# Control_de_Juez_V1_0_0.net
KiCad netlist of a schematic drawn in EAGLE
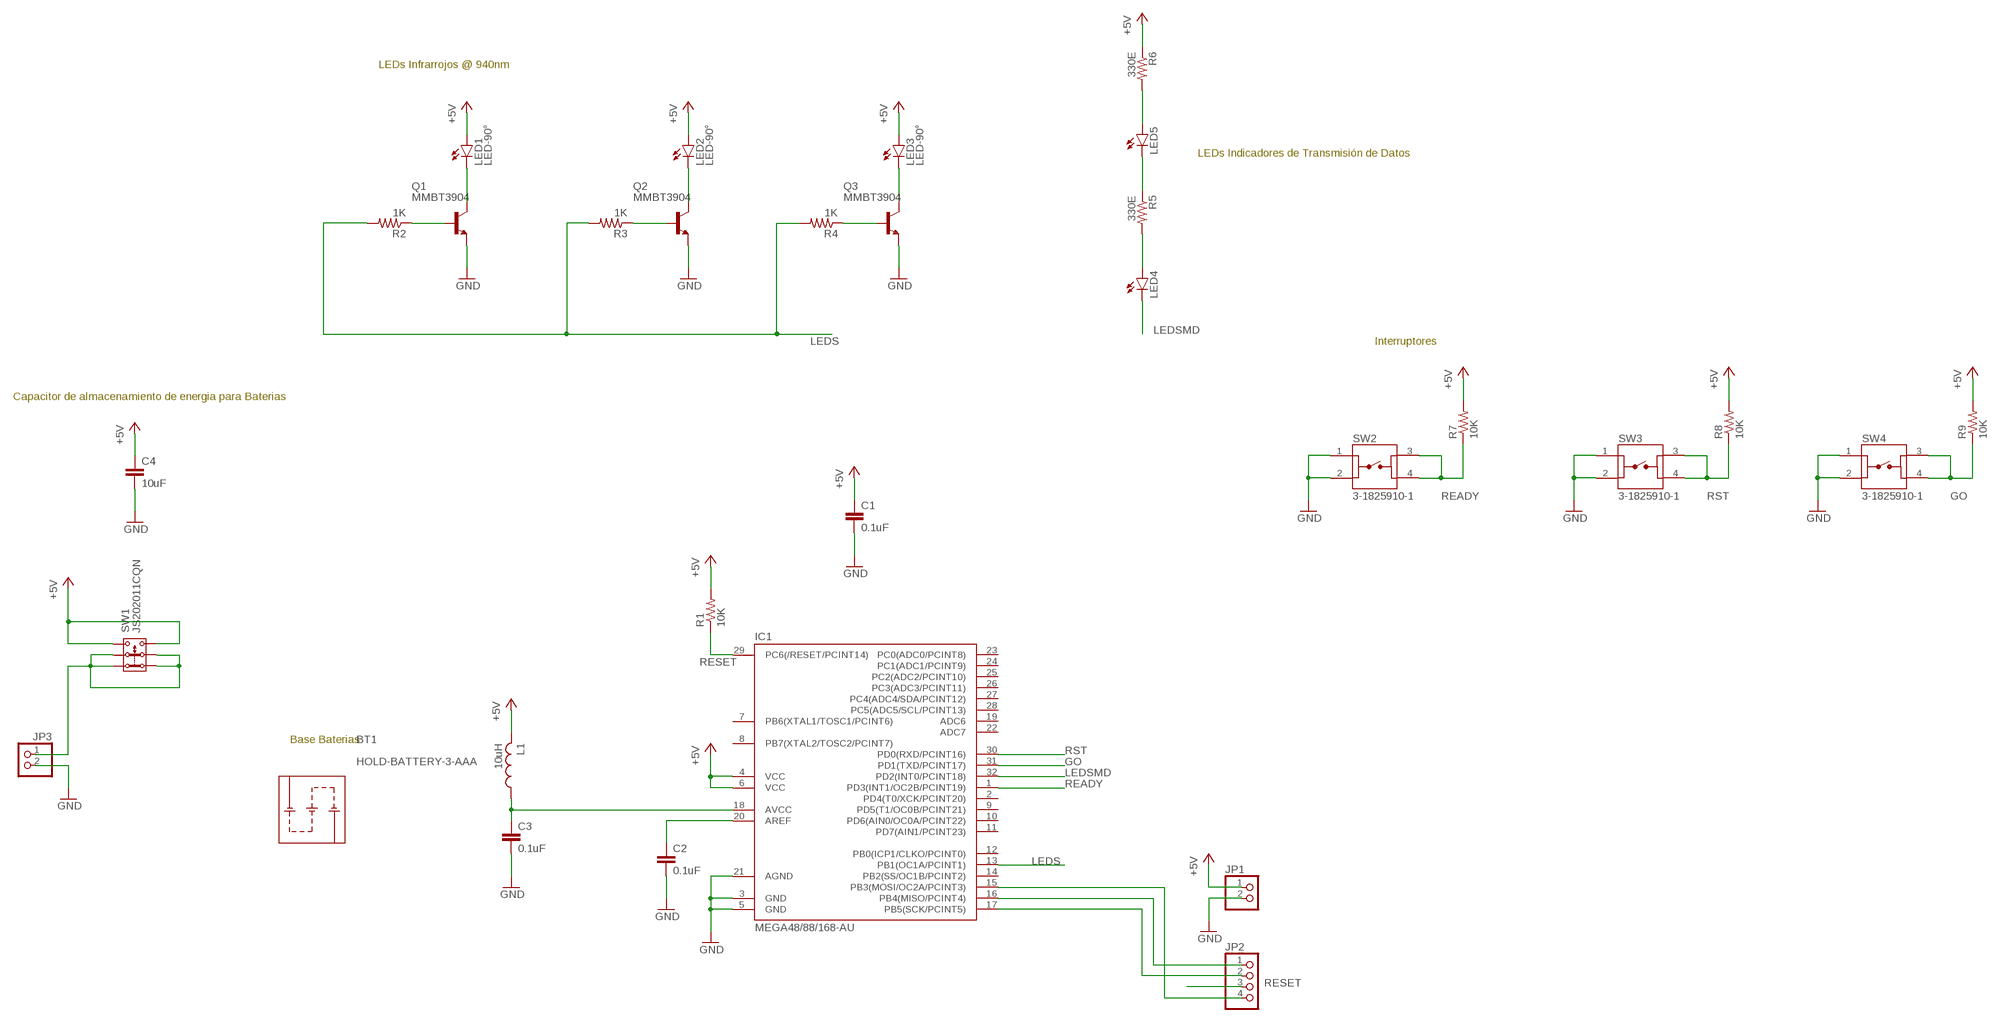
[diagram p0: schematic, sheet 1]

(export (version "E")
  (design (tool "Eeschema 10.0.6"))
  (components
    (comp (ref "BT1")
      (value "HOLD-BATTERY-3-AAA")
      (footprint "eagle-import:HOLDER-3-AAA")
      (libsource (lib "eagle-import") (part "HOLD-BATTERY-3-AAA"))
    )
    (comp (ref "C1")
      (value "0.1uF")
      (footprint "eagle-import:C0603")
      (libsource (lib "eagle-import") (part "C-EUC0603"))
    )
    (comp (ref "C2")
      (value "0.1uF")
      (footprint "eagle-import:C0603")
      (libsource (lib "eagle-import") (part "C-EUC0603"))
    )
    (comp (ref "C3")
      (value "0.1uF")
      (footprint "eagle-import:C0603")
      (libsource (lib "eagle-import") (part "C-EUC0603"))
    )
    (comp (ref "C4")
      (value "10uF")
      (footprint "eagle-import:C0603")
      (libsource (lib "eagle-import") (part "C-EUC0603"))
    )
    (comp (ref "IC1")
      (value "MEGA48/88/168-AU")
      (footprint "eagle-import:TQFP32-08")
      (libsource (lib "eagle-import") (part "MEGA48/88/168-AU"))
    )
    (comp (ref "JP1")
      (value "PINHD-1X02_2.54-S")
      (footprint "eagle-import:1X02-S")
      (libsource (lib "eagle-import") (part "PINHD-1X02_2.54-S"))
    )
    (comp (ref "JP2")
      (value "PINHD-1X04_2.54-S")
      (footprint "eagle-import:1X04-S")
      (libsource (lib "eagle-import") (part "PINHD-1X04_2.54-S"))
    )
    (comp (ref "JP3")
      (value "PINHD-1X02_2.54-S")
      (footprint "eagle-import:1X02-S")
      (libsource (lib "eagle-import") (part "PINHD-1X02_2.54-S"))
    )
    (comp (ref "L1")
      (value "10uH")
      (footprint "eagle-import:L1812")
      (libsource (lib "eagle-import") (part "L-USL1812"))
    )
    (comp (ref "LED1")
      (value "LED-90°")
      (footprint "eagle-import:LED-90°")
      (libsource (lib "eagle-import") (part "LED-90°"))
    )
    (comp (ref "LED2")
      (value "LED-90°")
      (footprint "eagle-import:LED-90°")
      (libsource (lib "eagle-import") (part "LED-90°"))
    )
    (comp (ref "LED3")
      (value "LED-90°")
      (footprint "eagle-import:LED-90°")
      (libsource (lib "eagle-import") (part "LED-90°"))
    )
    (comp (ref "LED4")
      (value "LEDCHIP-LED0603")
      (footprint "eagle-import:CHIP-LED0603")
      (libsource (lib "eagle-import") (part "LEDCHIP-LED0603"))
    )
    (comp (ref "LED5")
      (value "LEDCHIP-LED0603")
      (footprint "eagle-import:CHIP-LED0603")
      (libsource (lib "eagle-import") (part "LEDCHIP-LED0603"))
    )
    (comp (ref "Q1")
      (value "MMBT3904")
      (footprint "eagle-import:SOT23")
      (libsource (lib "eagle-import") (part "MMBT3904"))
    )
    (comp (ref "Q2")
      (value "MMBT3904")
      (footprint "eagle-import:SOT23")
      (libsource (lib "eagle-import") (part "MMBT3904"))
    )
    (comp (ref "Q3")
      (value "MMBT3904")
      (footprint "eagle-import:SOT23")
      (libsource (lib "eagle-import") (part "MMBT3904"))
    )
    (comp (ref "R1")
      (value "10K")
      (footprint "eagle-import:R0603")
      (libsource (lib "eagle-import") (part "R-US_R0603"))
    )
    (comp (ref "R2")
      (value "1K")
      (footprint "eagle-import:R0603")
      (libsource (lib "eagle-import") (part "R-US_R0603"))
    )
    (comp (ref "R3")
      (value "1K")
      (footprint "eagle-import:R0603")
      (libsource (lib "eagle-import") (part "R-US_R0603"))
    )
    (comp (ref "R4")
      (value "1K")
      (footprint "eagle-import:R0603")
      (libsource (lib "eagle-import") (part "R-US_R0603"))
    )
    (comp (ref "R5")
      (value "330E")
      (footprint "eagle-import:R0603")
      (libsource (lib "eagle-import") (part "R-US_R0603"))
    )
    (comp (ref "R6")
      (value "330E")
      (footprint "eagle-import:R0603")
      (libsource (lib "eagle-import") (part "R-US_R0603"))
    )
    (comp (ref "R7")
      (value "10K")
      (footprint "eagle-import:R0603")
      (libsource (lib "eagle-import") (part "R-US_R0603"))
    )
    (comp (ref "R8")
      (value "10K")
      (footprint "eagle-import:R0603")
      (libsource (lib "eagle-import") (part "R-US_R0603"))
    )
    (comp (ref "R9")
      (value "10K")
      (footprint "eagle-import:R0603")
      (libsource (lib "eagle-import") (part "R-US_R0603"))
    )
    (comp (ref "SW1")
      (value "JS202011CQN")
      (footprint "eagle-import:PTH")
      (libsource (lib "eagle-import") (part "JS202011CQN"))
    )
    (comp (ref "SW2")
      (value "3-1825910-1")
      (footprint "eagle-import:TE_3-1825910-1")
      (fields (field (name "MF") "TE Connectivity"))
      (libsource (lib "eagle-import") (part "3-1825910-1"))
    )
    (comp (ref "SW3")
      (value "3-1825910-1")
      (footprint "eagle-import:TE_3-1825910-1")
      (fields (field (name "MF") "TE Connectivity"))
      (libsource (lib "eagle-import") (part "3-1825910-1"))
    )
    (comp (ref "SW4")
      (value "3-1825910-1")
      (footprint "eagle-import:TE_3-1825910-1")
      (fields (field (name "MF") "TE Connectivity"))
      (libsource (lib "eagle-import") (part "3-1825910-1"))
    )
  )
  (nets
    (net (code "1") (name "+5V") (class "Default")
      (node (ref "C1") (pin "1") (pinfunction "1_1") (pintype "passive"))
      (node (ref "C4") (pin "1") (pinfunction "1_1") (pintype "passive"))
      (node (ref "IC1") (pin "4") (pinfunction "VCC_4") (pintype "power_in"))
      (node (ref "IC1") (pin "6") (pinfunction "VCC_6") (pintype "power_in"))
      (node (ref "JP1") (pin "1") (pinfunction "1_1") (pintype "passive"))
      (node (ref "L1") (pin "2") (pinfunction "2_2") (pintype "passive"))
      (node (ref "LED1") (pin "1") (pinfunction "A_1") (pintype "passive"))
      (node (ref "LED2") (pin "1") (pinfunction "A_1") (pintype "passive"))
      (node (ref "LED3") (pin "1") (pinfunction "A_1") (pintype "passive"))
      (node (ref "R1") (pin "2") (pinfunction "2_2") (pintype "passive"))
      (node (ref "R6") (pin "1") (pinfunction "1_1") (pintype "passive"))
      (node (ref "R7") (pin "2") (pinfunction "2_2") (pintype "passive"))
      (node (ref "R8") (pin "2") (pinfunction "2_2") (pintype "passive"))
      (node (ref "R9") (pin "2") (pinfunction "2_2") (pintype "passive"))
      (node (ref "SW1") (pin "3.1") (pinfunction "3.1_3.1") (pintype "passive"))
      (node (ref "SW1") (pin "3.2") (pinfunction "3.2_3.2") (pintype "passive"))
    )
    (net (code "2") (name "/GO") (class "Default")
      (node (ref "IC1") (pin "31") (pinfunction "PD1(TXD/PCINT17)_31") (pintype "bidirectional"))
      (node (ref "R9") (pin "1") (pinfunction "1_1") (pintype "passive"))
      (node (ref "SW4") (pin "3") (pinfunction "3_3") (pintype "passive"))
      (node (ref "SW4") (pin "4") (pinfunction "4_4") (pintype "passive"))
    )
    (net (code "3") (name "/LEDS") (class "Default")
      (node (ref "IC1") (pin "13") (pinfunction "PB1(OC1A/PCINT1)_13") (pintype "bidirectional"))
      (node (ref "R2") (pin "2") (pinfunction "2_2") (pintype "passive"))
      (node (ref "R3") (pin "2") (pinfunction "2_2") (pintype "passive"))
      (node (ref "R4") (pin "2") (pinfunction "2_2") (pintype "passive"))
    )
    (net (code "4") (name "/LEDSMD") (class "Default")
      (node (ref "IC1") (pin "32") (pinfunction "PD2(INT0/PCINT18)_32") (pintype "bidirectional"))
      (node (ref "LED4") (pin "C") (pinfunction "C_C") (pintype "passive"))
    )
    (net (code "5") (name "/READY") (class "Default")
      (node (ref "IC1") (pin "1") (pinfunction "PD3(INT1/OC2B/PCINT19)_1") (pintype "bidirectional"))
      (node (ref "R7") (pin "1") (pinfunction "1_1") (pintype "passive"))
      (node (ref "SW2") (pin "3") (pinfunction "3_3") (pintype "passive"))
      (node (ref "SW2") (pin "4") (pinfunction "4_4") (pintype "passive"))
    )
    (net (code "6") (name "/RESET") (class "Default")
      (node (ref "IC1") (pin "29") (pinfunction "PC6(/RESET/PCINT14)_29") (pintype "bidirectional"))
      (node (ref "JP2") (pin "3") (pinfunction "3_3") (pintype "passive"))
      (node (ref "R1") (pin "1") (pinfunction "1_1") (pintype "passive"))
    )
    (net (code "7") (name "/RST") (class "Default")
      (node (ref "IC1") (pin "30") (pinfunction "PD0(RXD/PCINT16)_30") (pintype "bidirectional"))
      (node (ref "R8") (pin "1") (pinfunction "1_1") (pintype "passive"))
      (node (ref "SW3") (pin "3") (pinfunction "3_3") (pintype "passive"))
      (node (ref "SW3") (pin "4") (pinfunction "4_4") (pintype "passive"))
    )
    (net (code "8") (name "GND") (class "Default")
      (node (ref "C1") (pin "2") (pinfunction "2_2") (pintype "passive"))
      (node (ref "C2") (pin "2") (pinfunction "2_2") (pintype "passive"))
      (node (ref "C3") (pin "2") (pinfunction "2_2") (pintype "passive"))
      (node (ref "C4") (pin "2") (pinfunction "2_2") (pintype "passive"))
      (node (ref "IC1") (pin "21") (pinfunction "AGND_21") (pintype "power_in"))
      (node (ref "IC1") (pin "3") (pinfunction "GND_3") (pintype "power_in"))
      (node (ref "IC1") (pin "5") (pinfunction "GND_5") (pintype "power_in"))
      (node (ref "JP1") (pin "2") (pinfunction "2_2") (pintype "passive"))
      (node (ref "JP3") (pin "2") (pinfunction "2_2") (pintype "passive"))
      (node (ref "Q1") (pin "E") (pinfunction "E_E") (pintype "passive"))
      (node (ref "Q2") (pin "E") (pinfunction "E_E") (pintype "passive"))
      (node (ref "Q3") (pin "E") (pinfunction "E_E") (pintype "passive"))
      (node (ref "SW2") (pin "1") (pinfunction "1_1") (pintype "passive"))
      (node (ref "SW2") (pin "2") (pinfunction "2_2") (pintype "passive"))
      (node (ref "SW3") (pin "1") (pinfunction "1_1") (pintype "passive"))
      (node (ref "SW3") (pin "2") (pinfunction "2_2") (pintype "passive"))
      (node (ref "SW4") (pin "1") (pinfunction "1_1") (pintype "passive"))
      (node (ref "SW4") (pin "2") (pinfunction "2_2") (pintype "passive"))
    )
    (net (code "9") (name "Net-(IC1-AREF)") (class "Default")
      (node (ref "C2") (pin "1") (pinfunction "1_1") (pintype "passive"))
      (node (ref "IC1") (pin "20") (pinfunction "AREF_20") (pintype "passive"))
    )
    (net (code "10") (name "Net-(IC1-AVCC)") (class "Default")
      (node (ref "C3") (pin "1") (pinfunction "1_1") (pintype "passive"))
      (node (ref "IC1") (pin "18") (pinfunction "AVCC_18") (pintype "passive"))
      (node (ref "L1") (pin "1") (pinfunction "1_1") (pintype "passive"))
    )
    (net (code "11") (name "Net-(IC1-PB3(MOSI{slash}OC2A{slash}PCINT3))") (class "Default")
      (node (ref "IC1") (pin "15") (pinfunction "PB3(MOSI/OC2A/PCINT3)_15") (pintype "bidirectional"))
      (node (ref "JP2") (pin "4") (pinfunction "4_4") (pintype "passive"))
    )
    (net (code "12") (name "Net-(IC1-PB4(MISO{slash}PCINT4))") (class "Default")
      (node (ref "IC1") (pin "16") (pinfunction "PB4(MISO/PCINT4)_16") (pintype "bidirectional"))
      (node (ref "JP2") (pin "1") (pinfunction "1_1") (pintype "passive"))
    )
    (net (code "13") (name "Net-(IC1-PB5(SCK{slash}PCINT5))") (class "Default")
      (node (ref "IC1") (pin "17") (pinfunction "PB5(SCK/PCINT5)_17") (pintype "bidirectional"))
      (node (ref "JP2") (pin "2") (pinfunction "2_2") (pintype "passive"))
    )
    (net (code "14") (name "Net-(JP3-Pad1)") (class "Default")
      (node (ref "JP3") (pin "1") (pinfunction "1_1") (pintype "passive"))
      (node (ref "SW1") (pin "1.1") (pinfunction "1.1_1.1") (pintype "passive"))
      (node (ref "SW1") (pin "1.2") (pinfunction "1.2_1.2") (pintype "passive"))
      (node (ref "SW1") (pin "2.1") (pinfunction "2.1_2.1") (pintype "passive"))
      (node (ref "SW1") (pin "2.2") (pinfunction "2.2_2.2") (pintype "passive"))
    )
    (net (code "15") (name "Net-(LED1-C)") (class "Default")
      (node (ref "LED1") (pin "2") (pinfunction "C_2") (pintype "passive"))
      (node (ref "Q1") (pin "C") (pinfunction "C_C") (pintype "passive"))
    )
    (net (code "16") (name "Net-(LED2-C)") (class "Default")
      (node (ref "LED2") (pin "2") (pinfunction "C_2") (pintype "passive"))
      (node (ref "Q2") (pin "C") (pinfunction "C_C") (pintype "passive"))
    )
    (net (code "17") (name "Net-(LED3-C)") (class "Default")
      (node (ref "LED3") (pin "2") (pinfunction "C_2") (pintype "passive"))
      (node (ref "Q3") (pin "C") (pinfunction "C_C") (pintype "passive"))
    )
    (net (code "18") (name "Net-(LED4-PadA)") (class "Default")
      (node (ref "LED4") (pin "A") (pinfunction "A_A") (pintype "passive"))
      (node (ref "R5") (pin "2") (pinfunction "2_2") (pintype "passive"))
    )
    (net (code "19") (name "Net-(LED5-PadA)") (class "Default")
      (node (ref "LED5") (pin "A") (pinfunction "A_A") (pintype "passive"))
      (node (ref "R6") (pin "2") (pinfunction "2_2") (pintype "passive"))
    )
    (net (code "20") (name "Net-(LED5-PadC)") (class "Default")
      (node (ref "LED5") (pin "C") (pinfunction "C_C") (pintype "passive"))
      (node (ref "R5") (pin "1") (pinfunction "1_1") (pintype "passive"))
    )
    (net (code "21") (name "Net-(Q1-PadB)") (class "Default")
      (node (ref "Q1") (pin "B") (pinfunction "B_B") (pintype "passive"))
      (node (ref "R2") (pin "1") (pinfunction "1_1") (pintype "passive"))
    )
    (net (code "22") (name "Net-(Q2-PadB)") (class "Default")
      (node (ref "Q2") (pin "B") (pinfunction "B_B") (pintype "passive"))
      (node (ref "R3") (pin "1") (pinfunction "1_1") (pintype "passive"))
    )
    (net (code "23") (name "Net-(Q3-PadB)") (class "Default")
      (node (ref "Q3") (pin "B") (pinfunction "B_B") (pintype "passive"))
      (node (ref "R4") (pin "1") (pinfunction "1_1") (pintype "passive"))
    )
    (net (code "24") (name "unconnected-(IC1-ADC6-Pad19)") (class "Default")
      (node (ref "IC1") (pin "19") (pinfunction "ADC6_19") (pintype "passive"))
    )
    (net (code "25") (name "unconnected-(IC1-ADC7-Pad22)") (class "Default")
      (node (ref "IC1") (pin "22") (pinfunction "ADC7_22") (pintype "passive"))
    )
    (net (code "26") (name "unconnected-(IC1-PB0(ICP1{slash}CLKO{slash}PCINT0)-Pad12)") (class "Default")
      (node (ref "IC1") (pin "12") (pinfunction "PB0(ICP1/CLKO/PCINT0)_12") (pintype "bidirectional"))
    )
    (net (code "27") (name "unconnected-(IC1-PB2(SS{slash}OC1B{slash}PCINT2)-Pad14)") (class "Default")
      (node (ref "IC1") (pin "14") (pinfunction "PB2(SS/OC1B/PCINT2)_14") (pintype "bidirectional"))
    )
    (net (code "28") (name "unconnected-(IC1-PB6(XTAL1{slash}TOSC1{slash}PCINT6)-Pad7)") (class "Default")
      (node (ref "IC1") (pin "7") (pinfunction "PB6(XTAL1/TOSC1/PCINT6)_7") (pintype "bidirectional"))
    )
    (net (code "29") (name "unconnected-(IC1-PB7(XTAL2{slash}TOSC2{slash}PCINT7)-Pad8)") (class "Default")
      (node (ref "IC1") (pin "8") (pinfunction "PB7(XTAL2/TOSC2/PCINT7)_8") (pintype "bidirectional"))
    )
    (net (code "30") (name "unconnected-(IC1-PC0(ADC0{slash}PCINT8)-Pad23)") (class "Default")
      (node (ref "IC1") (pin "23") (pinfunction "PC0(ADC0/PCINT8)_23") (pintype "bidirectional"))
    )
    (net (code "31") (name "unconnected-(IC1-PC1(ADC1{slash}PCINT9)-Pad24)") (class "Default")
      (node (ref "IC1") (pin "24") (pinfunction "PC1(ADC1/PCINT9)_24") (pintype "bidirectional"))
    )
    (net (code "32") (name "unconnected-(IC1-PC2(ADC2{slash}PCINT10)-Pad25)") (class "Default")
      (node (ref "IC1") (pin "25") (pinfunction "PC2(ADC2/PCINT10)_25") (pintype "bidirectional"))
    )
    (net (code "33") (name "unconnected-(IC1-PC3(ADC3{slash}PCINT11)-Pad26)") (class "Default")
      (node (ref "IC1") (pin "26") (pinfunction "PC3(ADC3/PCINT11)_26") (pintype "bidirectional"))
    )
    (net (code "34") (name "unconnected-(IC1-PC4(ADC4{slash}SDA{slash}PCINT12)-Pad27)") (class "Default")
      (node (ref "IC1") (pin "27") (pinfunction "PC4(ADC4/SDA/PCINT12)_27") (pintype "bidirectional"))
    )
    (net (code "35") (name "unconnected-(IC1-PC5(ADC5{slash}SCL{slash}PCINT13)-Pad28)") (class "Default")
      (node (ref "IC1") (pin "28") (pinfunction "PC5(ADC5/SCL/PCINT13)_28") (pintype "bidirectional"))
    )
    (net (code "36") (name "unconnected-(IC1-PD4(T0{slash}XCK{slash}PCINT20)-Pad2)") (class "Default")
      (node (ref "IC1") (pin "2") (pinfunction "PD4(T0/XCK/PCINT20)_2") (pintype "bidirectional"))
    )
    (net (code "37") (name "unconnected-(IC1-PD5(T1{slash}OC0B{slash}PCINT21)-Pad9)") (class "Default")
      (node (ref "IC1") (pin "9") (pinfunction "PD5(T1/OC0B/PCINT21)_9") (pintype "bidirectional"))
    )
    (net (code "38") (name "unconnected-(IC1-PD6(AIN0{slash}OC0A{slash}PCINT22)-Pad10)") (class "Default")
      (node (ref "IC1") (pin "10") (pinfunction "PD6(AIN0/OC0A/PCINT22)_10") (pintype "bidirectional"))
    )
    (net (code "39") (name "unconnected-(IC1-PD7(AIN1{slash}PCINT23)-Pad11)") (class "Default")
      (node (ref "IC1") (pin "11") (pinfunction "PD7(AIN1/PCINT23)_11") (pintype "bidirectional"))
    )
  )
)
